# hail-met-v0.net
KiCad netlist of a schematic drawn in EAGLE
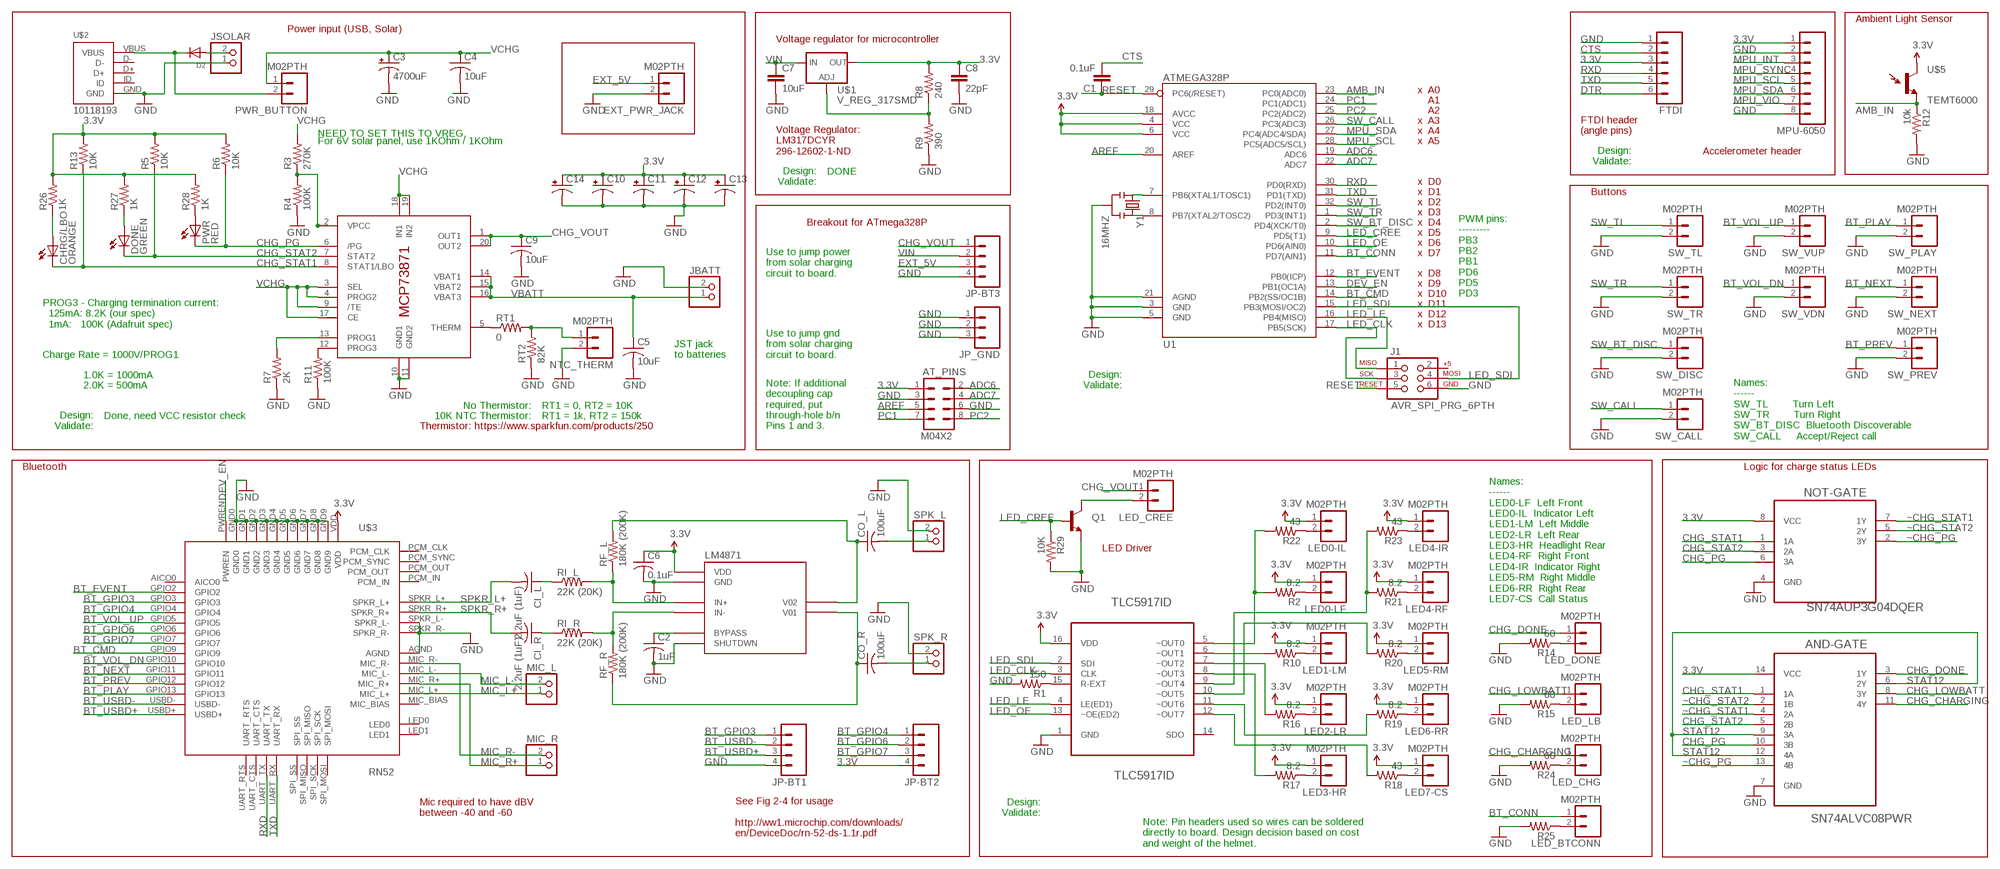
[diagram p0: schematic, sheet 1]

(export (version "E")
  (design (tool "Eeschema 10.0.6"))
  (components
    (comp (ref "AND-GATE")
      (value "SN74ALVC08PWR")
      (footprint "eagle-import:SOP65P640X120-14N")
      (libsource (lib "eagle-import") (part "SN74ALVC08PWR"))
    )
    (comp (ref "AT_PINS")
      (value "M04X2")
      (footprint "eagle-import:2X4")
      (libsource (lib "eagle-import") (part "M04X2"))
    )
    (comp (ref "C1")
      (value "0.1uF")
      (footprint "eagle-import:0805")
      (libsource (lib "eagle-import") (part "CAP0805"))
    )
    (comp (ref "C2")
      (value "1uF")
      (footprint "eagle-import:C0805K")
      (libsource (lib "eagle-import") (part "C-USC0805K"))
    )
    (comp (ref "C3")
      (value "4700uF")
      (footprint "eagle-import:E5-13")
      (libsource (lib "eagle-import") (part "CPOL-USE5-13"))
    )
    (comp (ref "C4")
      (value "10uF")
      (footprint "eagle-import:C0805K")
      (libsource (lib "eagle-import") (part "C-USC0805K"))
    )
    (comp (ref "C5")
      (value "10uF")
      (footprint "eagle-import:C0805K")
      (libsource (lib "eagle-import") (part "rcl_C-USC0805K"))
    )
    (comp (ref "C6")
      (value "0.1uF")
      (footprint "eagle-import:C0805K")
      (libsource (lib "eagle-import") (part "C-USC0805K"))
    )
    (comp (ref "C7")
      (value "10uF")
      (footprint "eagle-import:0805")
      (libsource (lib "eagle-import") (part "CAP0805"))
    )
    (comp (ref "C8")
      (value "22pF")
      (footprint "eagle-import:0805")
      (libsource (lib "eagle-import") (part "CAP0805"))
    )
    (comp (ref "C9")
      (value "10uF")
      (footprint "eagle-import:C0805K")
      (libsource (lib "eagle-import") (part "C-USC0805K"))
    )
    (comp (ref "C10")
      (value "CAP_POLPTH1")
      (footprint "eagle-import:CPOL-RADIAL-100UF-25V")
      (libsource (lib "eagle-import") (part "CAP_POLPTH1"))
    )
    (comp (ref "C11")
      (value "CAP_POLPTH1")
      (footprint "eagle-import:CPOL-RADIAL-100UF-25V")
      (libsource (lib "eagle-import") (part "CAP_POLPTH1"))
    )
    (comp (ref "C12")
      (value "CAP_POLPTH1")
      (footprint "eagle-import:CPOL-RADIAL-100UF-25V")
      (libsource (lib "eagle-import") (part "CAP_POLPTH1"))
    )
    (comp (ref "C13")
      (value "CAP_POLPTH1")
      (footprint "eagle-import:CPOL-RADIAL-100UF-25V")
      (libsource (lib "eagle-import") (part "CAP_POLPTH1"))
    )
    (comp (ref "C14")
      (value "CAP_POLPTH1")
      (footprint "eagle-import:CPOL-RADIAL-100UF-25V")
      (libsource (lib "eagle-import") (part "CAP_POLPTH1"))
    )
    (comp (ref "CHRG/LBO")
      (value "ORANGE")
      (footprint "eagle-import:CHIP-LED0805")
      (libsource (lib "eagle-import") (part "LEDCHIP-LED0805"))
    )
    (comp (ref "CI_L")
      (value "2.2uF (1uF)")
      (footprint "eagle-import:C0805K")
      (libsource (lib "eagle-import") (part "C-USC0805K"))
    )
    (comp (ref "CI_R")
      (value "2.2uF (1uF)")
      (footprint "eagle-import:C0805K")
      (libsource (lib "eagle-import") (part "C-USC0805K"))
    )
    (comp (ref "CO_L")
      (value "100uF")
      (footprint "eagle-import:C0805K")
      (libsource (lib "eagle-import") (part "C-USC0805K"))
    )
    (comp (ref "CO_R")
      (value "100uF")
      (footprint "eagle-import:C0805K")
      (libsource (lib "eagle-import") (part "C-USC0805K"))
    )
    (comp (ref "D2")
      (value "DIODESOD-123")
      (footprint "eagle-import:SOD-123")
      (libsource (lib "eagle-import") (part "DIODESOD-123"))
    )
    (comp (ref "DONE")
      (value "GREEN")
      (footprint "eagle-import:CHIP-LED0805")
      (libsource (lib "eagle-import") (part "LEDCHIP-LED0805"))
    )
    (comp (ref "EXT_PWR_JACK")
      (value "M02PTH")
      (footprint "eagle-import:1X02")
      (libsource (lib "eagle-import") (part "M02PTH"))
    )
    (comp (ref "FTDI")
      (value "M06LOCK")
      (footprint "eagle-import:1X06_LOCK")
      (libsource (lib "eagle-import") (part "M06LOCK"))
    )
    (comp (ref "IC1")
      (value "MCP73871")
      (footprint "eagle-import:QFN20")
      (libsource (lib "eagle-import") (part "MCP73871"))
    )
    (comp (ref "J1")
      (value "AVR_SPI_PRG_6PTH")
      (footprint "eagle-import:2X3")
      (libsource (lib "eagle-import") (part "AVR_SPI_PRG_6PTH"))
    )
    (comp (ref "JBATT")
      (value "JST_2PIN-SMT")
      (footprint "eagle-import:JST-PH-2-SMT")
      (libsource (lib "eagle-import") (part "JST_2PIN-SMT"))
    )
    (comp (ref "JP-BT1")
      (value "M04LOCK")
      (footprint "eagle-import:1X04_LOCK")
      (libsource (lib "eagle-import") (part "M04LOCK"))
    )
    (comp (ref "JP-BT2")
      (value "M04LOCK")
      (footprint "eagle-import:1X04_LOCK")
      (libsource (lib "eagle-import") (part "M04LOCK"))
    )
    (comp (ref "JP-BT3")
      (value "M04LOCK")
      (footprint "eagle-import:1X04_LOCK")
      (libsource (lib "eagle-import") (part "M04LOCK"))
    )
    (comp (ref "JP_GND")
      (value "M03LOCK")
      (footprint "eagle-import:1X03_LOCK")
      (libsource (lib "eagle-import") (part "M03LOCK"))
    )
    (comp (ref "JSOLAR")
      (value "JST_2PIN-SMT")
      (footprint "eagle-import:JST-PH-2-SMT")
      (libsource (lib "eagle-import") (part "JST_2PIN-SMT"))
    )
    (comp (ref "LED0-IL")
      (value "M02PTH")
      (footprint "eagle-import:1X02")
      (libsource (lib "eagle-import") (part "M02PTH"))
    )
    (comp (ref "LED0-LF")
      (value "M02PTH")
      (footprint "eagle-import:1X02")
      (libsource (lib "eagle-import") (part "M02PTH"))
    )
    (comp (ref "LED1-LM")
      (value "M02PTH")
      (footprint "eagle-import:1X02")
      (libsource (lib "eagle-import") (part "M02PTH"))
    )
    (comp (ref "LED2-LR")
      (value "M02PTH")
      (footprint "eagle-import:1X02")
      (libsource (lib "eagle-import") (part "M02PTH"))
    )
    (comp (ref "LED3-HR")
      (value "M02PTH")
      (footprint "eagle-import:1X02")
      (libsource (lib "eagle-import") (part "M02PTH"))
    )
    (comp (ref "LED4-IR")
      (value "M02PTH")
      (footprint "eagle-import:1X02")
      (libsource (lib "eagle-import") (part "M02PTH"))
    )
    (comp (ref "LED4-RF")
      (value "M02PTH")
      (footprint "eagle-import:1X02")
      (libsource (lib "eagle-import") (part "M02PTH"))
    )
    (comp (ref "LED5-RM")
      (value "M02PTH")
      (footprint "eagle-import:1X02")
      (libsource (lib "eagle-import") (part "M02PTH"))
    )
    (comp (ref "LED6-RR")
      (value "M02PTH")
      (footprint "eagle-import:1X02")
      (libsource (lib "eagle-import") (part "M02PTH"))
    )
    (comp (ref "LED7-CS")
      (value "M02PTH")
      (footprint "eagle-import:1X02")
      (libsource (lib "eagle-import") (part "M02PTH"))
    )
    (comp (ref "LED_BTCONN")
      (value "M02PTH")
      (footprint "eagle-import:1X02")
      (libsource (lib "eagle-import") (part "M02PTH"))
    )
    (comp (ref "LED_CHG")
      (value "M02PTH")
      (footprint "eagle-import:1X02")
      (libsource (lib "eagle-import") (part "M02PTH"))
    )
    (comp (ref "LED_CREE")
      (value "M02PTH")
      (footprint "eagle-import:1X02")
      (libsource (lib "eagle-import") (part "M02PTH"))
    )
    (comp (ref "LED_DONE")
      (value "M02PTH")
      (footprint "eagle-import:1X02")
      (libsource (lib "eagle-import") (part "M02PTH"))
    )
    (comp (ref "LED_LB")
      (value "M02PTH")
      (footprint "eagle-import:1X02")
      (libsource (lib "eagle-import") (part "M02PTH"))
    )
    (comp (ref "LM4871")
      (value "LM4871")
      (footprint "eagle-import:SO08")
      (libsource (lib "eagle-import") (part "LM4871"))
    )
    (comp (ref "MIC_L")
      (value "JST_2PIN-SMT")
      (footprint "eagle-import:JST-PH-2-SMT")
      (libsource (lib "eagle-import") (part "JST_2PIN-SMT"))
    )
    (comp (ref "MIC_R")
      (value "JST_2PIN-SMT")
      (footprint "eagle-import:JST-PH-2-SMT")
      (libsource (lib "eagle-import") (part "JST_2PIN-SMT"))
    )
    (comp (ref "MPU-6050")
      (value "M08LOCK")
      (footprint "eagle-import:1X08_LOCK")
      (libsource (lib "eagle-import") (part "M08LOCK"))
    )
    (comp (ref "NOT-GATE")
      (value "SN74AUP3G04DQER")
      (footprint "eagle-import:SON35P100X140X40-8N")
      (libsource (lib "eagle-import") (part "SN74AUP3G04DQER"))
    )
    (comp (ref "NTC_THERM")
      (value "M02PTH")
      (footprint "eagle-import:1X02")
      (libsource (lib "eagle-import") (part "M02PTH"))
    )
    (comp (ref "PWR")
      (value "RED")
      (footprint "eagle-import:CHIP-LED0805")
      (libsource (lib "eagle-import") (part "LEDCHIP-LED0805"))
    )
    (comp (ref "PWR_BUTTON")
      (value "M02PTH")
      (footprint "eagle-import:1X02")
      (libsource (lib "eagle-import") (part "M02PTH"))
    )
    (comp (ref "Q1")
      (value "TRANSISTOR_NPNSOT23-3")
      (footprint "eagle-import:SOT23-3")
      (libsource (lib "eagle-import") (part "TRANSISTOR_NPNSOT23-3"))
    )
    (comp (ref "R1")
      (value "150")
      (footprint "eagle-import:0805")
      (libsource (lib "eagle-import") (part "RESISTOR0805-RES"))
    )
    (comp (ref "R2")
      (value "8.2")
      (footprint "eagle-import:0805")
      (libsource (lib "eagle-import") (part "RESISTOR0805-RES"))
    )
    (comp (ref "R3")
      (value "270K")
      (footprint "eagle-import:0805")
      (libsource (lib "eagle-import") (part "RESISTOR0805-RES"))
    )
    (comp (ref "R4")
      (value "100K")
      (footprint "eagle-import:0805")
      (libsource (lib "eagle-import") (part "RESISTOR0805-RES"))
    )
    (comp (ref "R5")
      (value "10K")
      (footprint "eagle-import:0805")
      (libsource (lib "eagle-import") (part "RESISTOR0805-RES"))
    )
    (comp (ref "R6")
      (value "10K")
      (footprint "eagle-import:0805")
      (libsource (lib "eagle-import") (part "RESISTOR0805-RES"))
    )
    (comp (ref "R7")
      (value "2K")
      (footprint "eagle-import:0805")
      (libsource (lib "eagle-import") (part "RESISTOR0805-RES"))
    )
    (comp (ref "R8")
      (value "240")
      (footprint "eagle-import:0805")
      (libsource (lib "eagle-import") (part "RESISTOR0805-RES"))
    )
    (comp (ref "R9")
      (value "390")
      (footprint "eagle-import:0805")
      (libsource (lib "eagle-import") (part "RESISTOR0805-RES"))
    )
    (comp (ref "R10")
      (value "8.2")
      (footprint "eagle-import:0805")
      (libsource (lib "eagle-import") (part "RESISTOR0805-RES"))
    )
    (comp (ref "R11")
      (value "100K")
      (footprint "eagle-import:0805")
      (libsource (lib "eagle-import") (part "RESISTOR0805-RES"))
    )
    (comp (ref "R12")
      (value "10k")
      (footprint "eagle-import:0805")
      (libsource (lib "eagle-import") (part "RESISTOR0805-RES"))
    )
    (comp (ref "R13")
      (value "10K")
      (footprint "eagle-import:0805")
      (libsource (lib "eagle-import") (part "RESISTOR0805-RES"))
    )
    (comp (ref "R14")
      (value "60")
      (footprint "eagle-import:0805")
      (libsource (lib "eagle-import") (part "RESISTOR0805-RES"))
    )
    (comp (ref "R15")
      (value "60")
      (footprint "eagle-import:0805")
      (libsource (lib "eagle-import") (part "RESISTOR0805-RES"))
    )
    (comp (ref "R16")
      (value "8.2")
      (footprint "eagle-import:0805")
      (libsource (lib "eagle-import") (part "RESISTOR0805-RES"))
    )
    (comp (ref "R17")
      (value "8.2")
      (footprint "eagle-import:0805")
      (libsource (lib "eagle-import") (part "RESISTOR0805-RES"))
    )
    (comp (ref "R18")
      (value "43")
      (footprint "eagle-import:0805")
      (libsource (lib "eagle-import") (part "RESISTOR0805-RES"))
    )
    (comp (ref "R19")
      (value "8.2")
      (footprint "eagle-import:0805")
      (libsource (lib "eagle-import") (part "RESISTOR0805-RES"))
    )
    (comp (ref "R20")
      (value "8.2")
      (footprint "eagle-import:0805")
      (libsource (lib "eagle-import") (part "RESISTOR0805-RES"))
    )
    (comp (ref "R21")
      (value "8.2")
      (footprint "eagle-import:0805")
      (libsource (lib "eagle-import") (part "RESISTOR0805-RES"))
    )
    (comp (ref "R22")
      (value "43")
      (footprint "eagle-import:0805")
      (libsource (lib "eagle-import") (part "RESISTOR0805-RES"))
    )
    (comp (ref "R23")
      (value "43")
      (footprint "eagle-import:0805")
      (libsource (lib "eagle-import") (part "RESISTOR0805-RES"))
    )
    (comp (ref "R24")
      (value "60")
      (footprint "eagle-import:0805")
      (libsource (lib "eagle-import") (part "RESISTOR0805-RES"))
    )
    (comp (ref "R25")
      (value "RESISTOR0805-RES")
      (footprint "eagle-import:0805")
      (libsource (lib "eagle-import") (part "RESISTOR0805-RES"))
    )
    (comp (ref "R26")
      (value "1K")
      (footprint "eagle-import:0805")
      (libsource (lib "eagle-import") (part "RESISTOR0805-RES"))
    )
    (comp (ref "R27")
      (value "1K")
      (footprint "eagle-import:0805")
      (libsource (lib "eagle-import") (part "RESISTOR0805-RES"))
    )
    (comp (ref "R28")
      (value "1K")
      (footprint "eagle-import:0805")
      (libsource (lib "eagle-import") (part "RESISTOR0805-RES"))
    )
    (comp (ref "R29")
      (value "10K")
      (footprint "eagle-import:0805")
      (libsource (lib "eagle-import") (part "RESISTOR0805-RES"))
    )
    (comp (ref "RF_L")
      (value "180K (200K)")
      (footprint "eagle-import:0805")
      (libsource (lib "eagle-import") (part "RESISTOR0805-RES"))
    )
    (comp (ref "RF_R")
      (value "180K (200K)")
      (footprint "eagle-import:0805")
      (libsource (lib "eagle-import") (part "RESISTOR0805-RES"))
    )
    (comp (ref "RI_L")
      (value "22K (20K)")
      (footprint "eagle-import:0805")
      (libsource (lib "eagle-import") (part "RESISTOR0805-RES"))
    )
    (comp (ref "RI_R")
      (value "22K (20K)")
      (footprint "eagle-import:0805")
      (libsource (lib "eagle-import") (part "RESISTOR0805-RES"))
    )
    (comp (ref "RT1")
      (value "0")
      (footprint "eagle-import:0805")
      (libsource (lib "eagle-import") (part "RESISTOR0805-RES"))
    )
    (comp (ref "RT2")
      (value "82K")
      (footprint "eagle-import:0805")
      (libsource (lib "eagle-import") (part "RESISTOR0805-RES"))
    )
    (comp (ref "SPK_L")
      (value "JST_2PIN-SMT")
      (footprint "eagle-import:JST-PH-2-SMT")
      (libsource (lib "eagle-import") (part "JST_2PIN-SMT"))
    )
    (comp (ref "SPK_R")
      (value "JST_2PIN-SMT")
      (footprint "eagle-import:JST-PH-2-SMT")
      (libsource (lib "eagle-import") (part "JST_2PIN-SMT"))
    )
    (comp (ref "SW_CALL")
      (value "M02PTH")
      (footprint "eagle-import:1X02")
      (libsource (lib "eagle-import") (part "M02PTH"))
    )
    (comp (ref "SW_DISC")
      (value "M02PTH")
      (footprint "eagle-import:1X02")
      (libsource (lib "eagle-import") (part "M02PTH"))
    )
    (comp (ref "SW_NEXT")
      (value "M02PTH")
      (footprint "eagle-import:1X02")
      (libsource (lib "eagle-import") (part "M02PTH"))
    )
    (comp (ref "SW_PLAY")
      (value "M02PTH")
      (footprint "eagle-import:1X02")
      (libsource (lib "eagle-import") (part "M02PTH"))
    )
    (comp (ref "SW_PREV")
      (value "M02PTH")
      (footprint "eagle-import:1X02")
      (libsource (lib "eagle-import") (part "M02PTH"))
    )
    (comp (ref "SW_TL")
      (value "M02PTH")
      (footprint "eagle-import:1X02")
      (libsource (lib "eagle-import") (part "M02PTH"))
    )
    (comp (ref "SW_TR")
      (value "M02PTH")
      (footprint "eagle-import:1X02")
      (libsource (lib "eagle-import") (part "M02PTH"))
    )
    (comp (ref "SW_VDN")
      (value "M02PTH")
      (footprint "eagle-import:1X02")
      (libsource (lib "eagle-import") (part "M02PTH"))
    )
    (comp (ref "SW_VUP")
      (value "M02PTH")
      (footprint "eagle-import:1X02")
      (libsource (lib "eagle-import") (part "M02PTH"))
    )
    (comp (ref "TLC5917ID")
      (value "TLC5917ID")
      (footprint "eagle-import:SOIC127P600X175-16N")
      (libsource (lib "eagle-import") (part "TLC5917ID"))
    )
    (comp (ref "U$1")
      (value "V_REG_317SMD")
      (footprint "eagle-import:SOT223")
      (libsource (lib "eagle-import") (part "V_REG_317SMD"))
    )
    (comp (ref "U$2")
      (value "10118193")
      (footprint "eagle-import:10118193")
      (libsource (lib "eagle-import") (part "10118193"))
    )
    (comp (ref "U$3")
      (value "RN52")
      (footprint "eagle-import:RN52")
      (libsource (lib "eagle-import") (part "RN52"))
    )
    (comp (ref "U$5")
      (value "TEMT6000")
      (footprint "eagle-import:TEMT6000-SEN")
      (libsource (lib "eagle-import") (part "TEMT6000"))
    )
    (comp (ref "U1")
      (value "ATMEGA328P")
      (footprint "eagle-import:TQFP32-08")
      (libsource (lib "eagle-import") (part "ATMEGA328_SMT"))
    )
    (comp (ref "Y1")
      (value "16MHZ")
      (footprint "eagle-import:RESONATOR-SMD")
      (libsource (lib "eagle-import") (part "RESONATOR16MHZ"))
    )
  )
  (nets
    (net (code "1") (name "/ADC6") (class "Default")
      (node (ref "AT_PINS") (pin "2") (pinfunction "2_2") (pintype "passive"))
      (node (ref "U1") (pin "19") (pinfunction "ADC6_19") (pintype "bidirectional"))
    )
    (net (code "2") (name "/ADC7") (class "Default")
      (node (ref "AT_PINS") (pin "4") (pinfunction "4_4") (pintype "passive"))
      (node (ref "U1") (pin "22") (pinfunction "ADC7_22") (pintype "bidirectional"))
    )
    (net (code "3") (name "/AMB_IN") (class "Default")
      (node (ref "R12") (pin "1") (pinfunction "1_1") (pintype "passive"))
      (node (ref "U$5") (pin "EMITTER") (pinfunction "E1_EMITTER") (pintype "passive"))
      (node (ref "U1") (pin "23") (pinfunction "PC0(ADC0)_23") (pintype "bidirectional"))
    )
    (net (code "4") (name "/AREF") (class "Default")
      (node (ref "AT_PINS") (pin "5") (pinfunction "5_5") (pintype "passive"))
      (node (ref "U1") (pin "20") (pinfunction "AREF_20") (pintype "bidirectional"))
    )
    (net (code "5") (name "/BT_CMD") (class "Default")
      (node (ref "U$3") (pin "GPIO9") (pinfunction "GPIO9_GPIO9") (pintype "bidirectional"))
      (node (ref "U1") (pin "14") (pinfunction "PB2(SS/OC1B)_14") (pintype "bidirectional"))
    )
    (net (code "6") (name "/BT_CONN") (class "Default")
      (node (ref "LED_BTCONN") (pin "1") (pinfunction "1_1") (pintype "passive"))
      (node (ref "U1") (pin "11") (pinfunction "PD7(AIN1)_11") (pintype "bidirectional"))
    )
    (net (code "7") (name "/BT_EVENT") (class "Default")
      (node (ref "U$3") (pin "GPIO2") (pinfunction "GPIO2_GPIO2") (pintype "bidirectional"))
      (node (ref "U1") (pin "12") (pinfunction "PB0(ICP)_12") (pintype "bidirectional"))
    )
    (net (code "8") (name "/BT_GPIO3") (class "Default")
      (node (ref "JP-BT1") (pin "1") (pinfunction "1_1") (pintype "passive"))
      (node (ref "U$3") (pin "GPIO3") (pinfunction "GPIO3_GPIO3") (pintype "bidirectional"))
    )
    (net (code "9") (name "/BT_GPIO4") (class "Default")
      (node (ref "JP-BT2") (pin "1") (pinfunction "1_1") (pintype "passive"))
      (node (ref "U$3") (pin "GPIO4") (pinfunction "GPIO4_GPIO4") (pintype "bidirectional"))
    )
    (net (code "10") (name "/BT_GPIO6") (class "Default")
      (node (ref "JP-BT2") (pin "2") (pinfunction "2_2") (pintype "passive"))
      (node (ref "U$3") (pin "GPIO6") (pinfunction "GPIO6_GPIO6") (pintype "bidirectional"))
    )
    (net (code "11") (name "/BT_GPIO7") (class "Default")
      (node (ref "JP-BT2") (pin "3") (pinfunction "3_3") (pintype "passive"))
      (node (ref "U$3") (pin "GPIO7") (pinfunction "GPIO7_GPIO7") (pintype "bidirectional"))
    )
    (net (code "12") (name "/BT_NEXT") (class "Default")
      (node (ref "SW_NEXT") (pin "1") (pinfunction "1_1") (pintype "passive"))
      (node (ref "U$3") (pin "GPIO11") (pinfunction "GPIO11_GPIO11") (pintype "bidirectional"))
    )
    (net (code "13") (name "/BT_PLAY") (class "Default")
      (node (ref "SW_PLAY") (pin "1") (pinfunction "1_1") (pintype "passive"))
      (node (ref "U$3") (pin "GPIO13") (pinfunction "GPIO13_GPIO13") (pintype "bidirectional"))
    )
    (net (code "14") (name "/BT_PREV") (class "Default")
      (node (ref "SW_PREV") (pin "1") (pinfunction "1_1") (pintype "passive"))
      (node (ref "U$3") (pin "GPIO12") (pinfunction "GPIO12_GPIO12") (pintype "bidirectional"))
    )
    (net (code "15") (name "/BT_USBD+") (class "Default")
      (node (ref "JP-BT1") (pin "3") (pinfunction "3_3") (pintype "passive"))
      (node (ref "U$3") (pin "USBD+") (pinfunction "USBD+_USBD+") (pintype "bidirectional"))
    )
    (net (code "16") (name "/BT_USBD-") (class "Default")
      (node (ref "JP-BT1") (pin "2") (pinfunction "2_2") (pintype "passive"))
      (node (ref "U$3") (pin "USBD-") (pinfunction "USBD-_USBD-") (pintype "bidirectional"))
    )
    (net (code "17") (name "/BT_VOL_DN") (class "Default")
      (node (ref "SW_VDN") (pin "1") (pinfunction "1_1") (pintype "passive"))
      (node (ref "U$3") (pin "GPIO10") (pinfunction "GPIO10_GPIO10") (pintype "bidirectional"))
    )
    (net (code "18") (name "/BT_VOL_UP") (class "Default")
      (node (ref "SW_VUP") (pin "1") (pinfunction "1_1") (pintype "passive"))
      (node (ref "U$3") (pin "GPIO5") (pinfunction "GPIO5_GPIO5") (pintype "bidirectional"))
    )
    (net (code "19") (name "/CHG_CHARGING") (class "Default")
      (node (ref "AND-GATE") (pin "11") (pinfunction "4Y_11") (pintype "output"))
      (node (ref "LED_CHG") (pin "1") (pinfunction "1_1") (pintype "passive"))
    )
    (net (code "20") (name "/CHG_DONE") (class "Default")
      (node (ref "AND-GATE") (pin "3") (pinfunction "1Y_3") (pintype "output"))
      (node (ref "LED_DONE") (pin "1") (pinfunction "1_1") (pintype "passive"))
    )
    (net (code "21") (name "/CHG_LOWBATT") (class "Default")
      (node (ref "AND-GATE") (pin "8") (pinfunction "3Y_8") (pintype "output"))
      (node (ref "LED_LB") (pin "1") (pinfunction "1_1") (pintype "passive"))
    )
    (net (code "22") (name "/CHG_PG") (class "Default")
      (node (ref "AND-GATE") (pin "10") (pinfunction "3B_10") (pintype "input"))
      (node (ref "IC1") (pin "6") (pinfunction "/PG_6") (pintype "output"))
      (node (ref "NOT-GATE") (pin "6") (pinfunction "3A_6") (pintype "input"))
      (node (ref "PWR") (pin "C") (pinfunction "C_C") (pintype "passive"))
      (node (ref "R6") (pin "1") (pinfunction "1_1") (pintype "passive"))
    )
    (net (code "23") (name "/CHG_STAT1") (class "Default")
      (node (ref "AND-GATE") (pin "1") (pinfunction "1A_1") (pintype "input"))
      (node (ref "CHRG/LBO") (pin "C") (pinfunction "C_C") (pintype "passive"))
      (node (ref "IC1") (pin "8") (pinfunction "STAT1/LBO_8") (pintype "output"))
      (node (ref "NOT-GATE") (pin "1") (pinfunction "1A_1") (pintype "input"))
      (node (ref "R13") (pin "1") (pinfunction "1_1") (pintype "passive"))
    )
    (net (code "24") (name "/CHG_STAT2") (class "Default")
      (node (ref "AND-GATE") (pin "5") (pinfunction "2B_5") (pintype "input"))
      (node (ref "DONE") (pin "C") (pinfunction "C_C") (pintype "passive"))
      (node (ref "IC1") (pin "7") (pinfunction "STAT2_7") (pintype "output"))
      (node (ref "NOT-GATE") (pin "3") (pinfunction "2A_3") (pintype "input"))
      (node (ref "R5") (pin "1") (pinfunction "1_1") (pintype "passive"))
    )
    (net (code "25") (name "/CHG_VOUT") (class "Default")
      (node (ref "C9") (pin "1") (pinfunction "1_1") (pintype "passive"))
      (node (ref "IC1") (pin "1") (pinfunction "OUT1_1") (pintype "output"))
      (node (ref "IC1") (pin "20") (pinfunction "OUT2_20") (pintype "output"))
      (node (ref "JP-BT3") (pin "1") (pinfunction "1_1") (pintype "passive"))
      (node (ref "LED_CREE") (pin "1") (pinfunction "1_1") (pintype "passive"))
    )
    (net (code "26") (name "/CTS") (class "Default")
      (node (ref "C1") (pin "2") (pinfunction "2_2") (pintype "passive"))
      (node (ref "FTDI") (pin "2") (pinfunction "2_2") (pintype "passive"))
    )
    (net (code "27") (name "/DEV_EN") (class "Default")
      (node (ref "U$3") (pin "PWREN") (pinfunction "PWREN_PWREN") (pintype "bidirectional"))
      (node (ref "U1") (pin "13") (pinfunction "PB1(OC1A)_13") (pintype "bidirectional"))
    )
    (net (code "28") (name "/DTR") (class "Default")
      (node (ref "FTDI") (pin "6") (pinfunction "6_6") (pintype "passive"))
    )
    (net (code "29") (name "/EXT_5V") (class "Default")
      (node (ref "EXT_PWR_JACK") (pin "1") (pinfunction "1_1") (pintype "passive"))
      (node (ref "JP-BT3") (pin "3") (pinfunction "3_3") (pintype "passive"))
    )
    (net (code "30") (name "/LED_CLK") (class "Default")
      (node (ref "J1") (pin "3") (pinfunction "3_3") (pintype "passive"))
      (node (ref "TLC5917ID") (pin "3") (pinfunction "CLK_3") (pintype "input"))
      (node (ref "U1") (pin "17") (pinfunction "PB5(SCK)_17") (pintype "bidirectional"))
    )
    (net (code "31") (name "/LED_CREE") (class "Default")
      (node (ref "Q1") (pin "1") (pinfunction "B_1") (pintype "passive"))
      (node (ref "R29") (pin "1") (pinfunction "1_1") (pintype "passive"))
      (node (ref "U1") (pin "9") (pinfunction "PD5(T1)_9") (pintype "bidirectional"))
    )
    (net (code "32") (name "/LED_LE") (class "Default")
      (node (ref "J1") (pin "1") (pinfunction "1_1") (pintype "passive"))
      (node (ref "TLC5917ID") (pin "4") (pinfunction "LE(ED1)_4") (pintype "input"))
      (node (ref "U1") (pin "16") (pinfunction "PB4(MISO)_16") (pintype "bidirectional"))
    )
    (net (code "33") (name "/LED_OE") (class "Default")
      (node (ref "TLC5917ID") (pin "13") (pinfunction "~{OE(ED2})_13") (pintype "input"))
      (node (ref "U1") (pin "10") (pinfunction "PD6(AIN0)_10") (pintype "bidirectional"))
    )
    (net (code "34") (name "/LED_SDI") (class "Default")
      (node (ref "J1") (pin "4") (pinfunction "4_4") (pintype "passive"))
      (node (ref "TLC5917ID") (pin "2") (pinfunction "SDI_2") (pintype "input"))
      (node (ref "U1") (pin "15") (pinfunction "PB3(MOSI/OC2)_15") (pintype "bidirectional"))
    )
    (net (code "35") (name "/MIC_L+") (class "Default")
      (node (ref "MIC_L") (pin "1") (pinfunction "2_1") (pintype "passive"))
      (node (ref "U$3") (pin "MIC_L+") (pinfunction "MIC_L+_MIC_L+") (pintype "bidirectional"))
    )
    (net (code "36") (name "/MIC_L-") (class "Default")
      (node (ref "MIC_L") (pin "2") (pinfunction "1_2") (pintype "passive"))
      (node (ref "U$3") (pin "MIC_L-") (pinfunction "MIC_L-_MIC_L-") (pintype "bidirectional"))
    )
    (net (code "37") (name "/MIC_R+") (class "Default")
      (node (ref "MIC_R") (pin "1") (pinfunction "2_1") (pintype "passive"))
      (node (ref "U$3") (pin "MIC_R+") (pinfunction "MIC_R+_MIC_R+") (pintype "bidirectional"))
    )
    (net (code "38") (name "/MIC_R-") (class "Default")
      (node (ref "MIC_R") (pin "2") (pinfunction "1_2") (pintype "passive"))
      (node (ref "U$3") (pin "MIC_R-") (pinfunction "MIC_R-_MIC_R-") (pintype "bidirectional"))
    )
    (net (code "39") (name "/MPU_INT") (class "Default")
      (node (ref "MPU-6050") (pin "3") (pinfunction "3_3") (pintype "passive"))
    )
    (net (code "40") (name "/MPU_SCL") (class "Default")
      (node (ref "MPU-6050") (pin "5") (pinfunction "5_5") (pintype "passive"))
      (node (ref "U1") (pin "28") (pinfunction "PC5(ADC5/SCL)_28") (pintype "bidirectional"))
    )
    (net (code "41") (name "/MPU_SDA") (class "Default")
      (node (ref "MPU-6050") (pin "6") (pinfunction "6_6") (pintype "passive"))
      (node (ref "U1") (pin "27") (pinfunction "PC4(ADC4/SDA)_27") (pintype "bidirectional"))
    )
    (net (code "42") (name "/MPU_SYNC") (class "Default")
      (node (ref "MPU-6050") (pin "4") (pinfunction "4_4") (pintype "passive"))
    )
    (net (code "43") (name "/MPU_VIO") (class "Default")
      (node (ref "MPU-6050") (pin "7") (pinfunction "7_7") (pintype "passive"))
    )
    (net (code "44") (name "/PC1") (class "Default")
      (node (ref "AT_PINS") (pin "7") (pinfunction "7_7") (pintype "passive"))
      (node (ref "U1") (pin "24") (pinfunction "PC1(ADC1)_24") (pintype "bidirectional"))
    )
    (net (code "45") (name "/PC2") (class "Default")
      (node (ref "AT_PINS") (pin "8") (pinfunction "8_8") (pintype "passive"))
      (node (ref "U1") (pin "25") (pinfunction "PC2(ADC2)_25") (pintype "bidirectional"))
    )
    (net (code "46") (name "/RESET") (class "Default")
      (node (ref "C1") (pin "1") (pinfunction "1_1") (pintype "passive"))
      (node (ref "J1") (pin "5") (pinfunction "5_5") (pintype "passive"))
      (node (ref "U1") (pin "29") (pinfunction "PC6(/RESET)_29") (pintype "bidirectional"))
    )
    (net (code "47") (name "/RXD") (class "Default")
      (node (ref "FTDI") (pin "4") (pinfunction "4_4") (pintype "passive"))
      (node (ref "U$3") (pin "UART_TX") (pinfunction "UART_TX_UART_TX") (pintype "bidirectional"))
      (node (ref "U1") (pin "30") (pinfunction "PD0(RXD)_30") (pintype "bidirectional"))
    )
    (net (code "48") (name "/SPKR_L+") (class "Default")
      (node (ref "CI_L") (pin "2") (pinfunction "2_2") (pintype "passive"))
      (node (ref "U$3") (pin "SPKR_L+") (pinfunction "SPKR_L+_SPKR_L+") (pintype "bidirectional"))
    )
    (net (code "49") (name "/SPKR_R+") (class "Default")
      (node (ref "CI_R") (pin "2") (pinfunction "2_2") (pintype "passive"))
      (node (ref "U$3") (pin "SPKR_R+") (pinfunction "SPKR_R+_SPKR_R+") (pintype "bidirectional"))
    )
    (net (code "50") (name "/STAT12") (class "Default")
      (node (ref "AND-GATE") (pin "12") (pinfunction "4A_12") (pintype "input"))
      (node (ref "AND-GATE") (pin "6") (pinfunction "2Y_6") (pintype "output"))
      (node (ref "AND-GATE") (pin "9") (pinfunction "3A_9") (pintype "input"))
    )
    (net (code "51") (name "/SW_BT_DISC") (class "Default")
      (node (ref "SW_DISC") (pin "1") (pinfunction "1_1") (pintype "passive"))
      (node (ref "U1") (pin "2") (pinfunction "PD4(XCK/T0)_2") (pintype "bidirectional"))
    )
    (net (code "52") (name "/SW_CALL") (class "Default")
      (node (ref "SW_CALL") (pin "1") (pinfunction "1_1") (pintype "passive"))
      (node (ref "U1") (pin "26") (pinfunction "PC3(ADC3)_26") (pintype "bidirectional"))
    )
    (net (code "53") (name "/SW_TL") (class "Default")
      (node (ref "SW_TL") (pin "1") (pinfunction "1_1") (pintype "passive"))
      (node (ref "U1") (pin "32") (pinfunction "PD2(INT0)_32") (pintype "bidirectional"))
    )
    (net (code "54") (name "/SW_TR") (class "Default")
      (node (ref "SW_TR") (pin "1") (pinfunction "1_1") (pintype "passive"))
      (node (ref "U1") (pin "1") (pinfunction "PD3(INT1)_1") (pintype "bidirectional"))
    )
    (net (code "55") (name "/TXD") (class "Default")
      (node (ref "FTDI") (pin "5") (pinfunction "5_5") (pintype "passive"))
      (node (ref "U$3") (pin "UART_RX") (pinfunction "UART_RX_UART_RX") (pintype "bidirectional"))
      (node (ref "U1") (pin "31") (pinfunction "PD1(TXD)_31") (pintype "bidirectional"))
    )
    (net (code "56") (name "/VBATT") (class "Default")
      (node (ref "C5") (pin "1") (pinfunction "1_1") (pintype "passive"))
      (node (ref "IC1") (pin "14") (pinfunction "VBAT1_14") (pintype "output"))
      (node (ref "IC1") (pin "15") (pinfunction "VBAT2_15") (pintype "output"))
      (node (ref "IC1") (pin "16") (pinfunction "VBAT3_16") (pintype "output"))
      (node (ref "JBATT") (pin "1") (pinfunction "2_1") (pintype "passive"))
    )
    (net (code "57") (name "/VCHG") (class "Default")
      (node (ref "C3") (pin "+") (pinfunction "+_+") (pintype "passive"))
      (node (ref "C4") (pin "1") (pinfunction "1_1") (pintype "passive"))
      (node (ref "IC1") (pin "17") (pinfunction "CE_17") (pintype "input"))
      (node (ref "IC1") (pin "18") (pinfunction "IN1_18") (pintype "input"))
      (node (ref "IC1") (pin "19") (pinfunction "IN2_19") (pintype "input"))
      (node (ref "IC1") (pin "3") (pinfunction "SEL_3") (pintype "input"))
      (node (ref "IC1") (pin "4") (pinfunction "PROG2_4") (pintype "input"))
      (node (ref "IC1") (pin "9") (pinfunction "/TE_9") (pintype "input"))
      (node (ref "PWR_BUTTON") (pin "1") (pinfunction "1_1") (pintype "passive"))
      (node (ref "R3") (pin "2") (pinfunction "2_2") (pintype "passive"))
    )
    (net (code "58") (name "/VIN") (class "Default")
      (node (ref "C7") (pin "1") (pinfunction "1_1") (pintype "passive"))
      (node (ref "JP-BT3") (pin "2") (pinfunction "2_2") (pintype "passive"))
      (node (ref "U$1") (pin "3") (pinfunction "IN_3") (pintype "input"))
    )
    (net (code "59") (name "/~{CHG_PG}") (class "Default")
      (node (ref "AND-GATE") (pin "13") (pinfunction "4B_13") (pintype "input"))
      (node (ref "NOT-GATE") (pin "2") (pinfunction "3Y_2") (pintype "output"))
    )
    (net (code "60") (name "/~{CHG_STAT1}") (class "Default")
      (node (ref "AND-GATE") (pin "4") (pinfunction "2A_4") (pintype "input"))
      (node (ref "NOT-GATE") (pin "7") (pinfunction "1Y_7") (pintype "output"))
    )
    (net (code "61") (name "/~{CHG_STAT2}") (class "Default")
      (node (ref "AND-GATE") (pin "2") (pinfunction "1B_2") (pintype "input"))
      (node (ref "NOT-GATE") (pin "5") (pinfunction "2Y_5") (pintype "output"))
    )
    (net (code "62") (name "3.3V") (class "Default")
      (node (ref "AND-GATE") (pin "14") (pinfunction "VCC_14") (pintype "power_in"))
      (node (ref "AT_PINS") (pin "1") (pinfunction "1_1") (pintype "passive"))
      (node (ref "C10") (pin "1") (pinfunction "+_1") (pintype "passive"))
      (node (ref "C11") (pin "1") (pinfunction "+_1") (pintype "passive"))
      (node (ref "C12") (pin "1") (pinfunction "+_1") (pintype "passive"))
      (node (ref "C13") (pin "1") (pinfunction "+_1") (pintype "passive"))
      (node (ref "C14") (pin "1") (pinfunction "+_1") (pintype "passive"))
      (node (ref "C6") (pin "1") (pinfunction "1_1") (pintype "passive"))
      (node (ref "C8") (pin "1") (pinfunction "1_1") (pintype "passive"))
      (node (ref "FTDI") (pin "3") (pinfunction "3_3") (pintype "passive"))
      (node (ref "JP-BT2") (pin "4") (pinfunction "4_4") (pintype "passive"))
      (node (ref "LED0-IL") (pin "1") (pinfunction "1_1") (pintype "passive"))
      (node (ref "LED0-LF") (pin "1") (pinfunction "1_1") (pintype "passive"))
      (node (ref "LED1-LM") (pin "1") (pinfunction "1_1") (pintype "passive"))
      (node (ref "LED2-LR") (pin "1") (pinfunction "1_1") (pintype "passive"))
      (node (ref "LED3-HR") (pin "1") (pinfunction "1_1") (pintype "passive"))
      (node (ref "LED4-IR") (pin "1") (pinfunction "1_1") (pintype "passive"))
      (node (ref "LED4-RF") (pin "1") (pinfunction "1_1") (pintype "passive"))
      (node (ref "LED5-RM") (pin "1") (pinfunction "1_1") (pintype "passive"))
      (node (ref "LED6-RR") (pin "1") (pinfunction "1_1") (pintype "passive"))
      (node (ref "LED7-CS") (pin "1") (pinfunction "1_1") (pintype "passive"))
      (node (ref "LM4871") (pin "6") (pinfunction "VDD_6") (pintype "bidirectional"))
      (node (ref "MPU-6050") (pin "1") (pinfunction "1_1") (pintype "passive"))
      (node (ref "NOT-GATE") (pin "8") (pinfunction "VCC_8") (pintype "power_in"))
      (node (ref "R13") (pin "2") (pinfunction "2_2") (pintype "passive"))
      (node (ref "R26") (pin "2") (pinfunction "2_2") (pintype "passive"))
      (node (ref "R27") (pin "2") (pinfunction "2_2") (pintype "passive"))
      (node (ref "R28") (pin "2") (pinfunction "2_2") (pintype "passive"))
      (node (ref "R5") (pin "2") (pinfunction "2_2") (pintype "passive"))
      (node (ref "R6") (pin "2") (pinfunction "2_2") (pintype "passive"))
      (node (ref "R8") (pin "2") (pinfunction "2_2") (pintype "passive"))
      (node (ref "TLC5917ID") (pin "16") (pinfunction "VDD_16") (pintype "power_in"))
      (node (ref "U$1") (pin "2") (pinfunction "OUT_2") (pintype "output"))
      (node (ref "U$3") (pin "VDD") (pinfunction "VDD_VDD") (pintype "bidirectional"))
      (node (ref "U$5") (pin "COLLECTOR") (pinfunction "C1_COLLECTOR") (pintype "passive"))
      (node (ref "U1") (pin "18") (pinfunction "AVCC_18") (pintype "bidirectional"))
      (node (ref "U1") (pin "4") (pinfunction "VCC_4") (pintype "bidirectional"))
      (node (ref "U1") (pin "6") (pinfunction "VCC_6") (pintype "bidirectional"))
    )
    (net (code "63") (name "GND") (class "Default")
      (node (ref "AND-GATE") (pin "7") (pinfunction "GND_7") (pintype "passive"))
      (node (ref "AT_PINS") (pin "3") (pinfunction "3_3") (pintype "passive"))
      (node (ref "AT_PINS") (pin "6") (pinfunction "6_6") (pintype "passive"))
      (node (ref "C10") (pin "2") (pinfunction "-_2") (pintype "passive"))
      (node (ref "C11") (pin "2") (pinfunction "-_2") (pintype "passive"))
      (node (ref "C12") (pin "2") (pinfunction "-_2") (pintype "passive"))
      (node (ref "C13") (pin "2") (pinfunction "-_2") (pintype "passive"))
      (node (ref "C14") (pin "2") (pinfunction "-_2") (pintype "passive"))
      (node (ref "C2") (pin "2") (pinfunction "2_2") (pintype "passive"))
      (node (ref "C3") (pin "-") (pinfunction "-_-") (pintype "passive"))
      (node (ref "C4") (pin "2") (pinfunction "2_2") (pintype "passive"))
      (node (ref "C5") (pin "2") (pinfunction "2_2") (pintype "passive"))
      (node (ref "C6") (pin "2") (pinfunction "2_2") (pintype "passive"))
      (node (ref "C7") (pin "2") (pinfunction "2_2") (pintype "passive"))
      (node (ref "C8") (pin "2") (pinfunction "2_2") (pintype "passive"))
      (node (ref "C9") (pin "2") (pinfunction "2_2") (pintype "passive"))
      (node (ref "EXT_PWR_JACK") (pin "2") (pinfunction "2_2") (pintype "passive"))
      (node (ref "FTDI") (pin "1") (pinfunction "1_1") (pintype "passive"))
      (node (ref "IC1") (pin "10") (pinfunction "GND1_10") (pintype "power_in"))
      (node (ref "IC1") (pin "11") (pinfunction "GND2_11") (pintype "power_in"))
      (node (ref "J1") (pin "6") (pinfunction "6_6") (pintype "passive"))
      (node (ref "JBATT") (pin "2") (pinfunction "1_2") (pintype "passive"))
      (node (ref "JP-BT1") (pin "4") (pinfunction "4_4") (pintype "passive"))
      (node (ref "JP-BT3") (pin "4") (pinfunction "4_4") (pintype "passive"))
      (node (ref "JP_GND") (pin "1") (pinfunction "1_1") (pintype "passive"))
      (node (ref "JP_GND") (pin "2") (pinfunction "2_2") (pintype "passive"))
      (node (ref "JP_GND") (pin "3") (pinfunction "3_3") (pintype "passive"))
      (node (ref "JSOLAR") (pin "1") (pinfunction "2_1") (pintype "passive"))
      (node (ref "LM4871") (pin "1") (pinfunction "SHUTDWN_1") (pintype "bidirectional"))
      (node (ref "LM4871") (pin "7") (pinfunction "GND_7") (pintype "bidirectional"))
      (node (ref "MPU-6050") (pin "2") (pinfunction "2_2") (pintype "passive"))
      (node (ref "MPU-6050") (pin "8") (pinfunction "8_8") (pintype "passive"))
      (node (ref "NOT-GATE") (pin "4") (pinfunction "GND_4") (pintype "passive"))
      (node (ref "NTC_THERM") (pin "2") (pinfunction "2_2") (pintype "passive"))
      (node (ref "Q1") (pin "2") (pinfunction "E_2") (pintype "passive"))
      (node (ref "R1") (pin "2") (pinfunction "2_2") (pintype "passive"))
      (node (ref "R11") (pin "1") (pinfunction "1_1") (pintype "passive"))
      (node (ref "R12") (pin "2") (pinfunction "2_2") (pintype "passive"))
      (node (ref "R14") (pin "2") (pinfunction "2_2") (pintype "passive"))
      (node (ref "R15") (pin "2") (pinfunction "2_2") (pintype "passive"))
      (node (ref "R24") (pin "2") (pinfunction "2_2") (pintype "passive"))
      (node (ref "R25") (pin "2") (pinfunction "2_2") (pintype "passive"))
      (node (ref "R29") (pin "2") (pinfunction "2_2") (pintype "passive"))
      (node (ref "R4") (pin "1") (pinfunction "1_1") (pintype "passive"))
      (node (ref "R7") (pin "1") (pinfunction "1_1") (pintype "passive"))
      (node (ref "R9") (pin "1") (pinfunction "1_1") (pintype "passive"))
      (node (ref "RT2") (pin "1") (pinfunction "1_1") (pintype "passive"))
      (node (ref "SPK_L") (pin "2") (pinfunction "1_2") (pintype "passive"))
      (node (ref "SPK_R") (pin "2") (pinfunction "1_2") (pintype "passive"))
      (node (ref "SW_CALL") (pin "2") (pinfunction "2_2") (pintype "passive"))
      (node (ref "SW_DISC") (pin "2") (pinfunction "2_2") (pintype "passive"))
      (node (ref "SW_NEXT") (pin "2") (pinfunction "2_2") (pintype "passive"))
      (node (ref "SW_PLAY") (pin "2") (pinfunction "2_2") (pintype "passive"))
      (node (ref "SW_PREV") (pin "2") (pinfunction "2_2") (pintype "passive"))
      (node (ref "SW_TL") (pin "2") (pinfunction "2_2") (pintype "passive"))
      (node (ref "SW_TR") (pin "2") (pinfunction "2_2") (pintype "passive"))
      (node (ref "SW_VDN") (pin "2") (pinfunction "2_2") (pintype "passive"))
      (node (ref "SW_VUP") (pin "2") (pinfunction "2_2") (pintype "passive"))
      (node (ref "TLC5917ID") (pin "1") (pinfunction "GND_1") (pintype "passive"))
      (node (ref "U$2") (pin "GND") (pinfunction "GND_GND") (pintype "bidirectional"))
      (node (ref "U$3") (pin "AGND") (pinfunction "AGND_AGND") (pintype "bidirectional"))
      (node (ref "U$3") (pin "GND0") (pinfunction "GND0_GND0") (pintype "bidirectional"))
      (node (ref "U$3") (pin "GND1") (pinfunction "GND1_GND1") (pintype "bidirectional"))
      (node (ref "U$3") (pin "GND2") (pinfunction "GND2_GND2") (pintype "bidirectional"))
      (node (ref "U$3") (pin "GND3") (pinfunction "GND3_GND3") (pintype "bidirectional"))
      (node (ref "U$3") (pin "GND4") (pinfunction "GND4_GND4") (pintype "bidirectional"))
      (node (ref "U$3") (pin "GND5") (pinfunction "GND5_GND5") (pintype "bidirectional"))
      (node (ref "U$3") (pin "GND6") (pinfunction "GND6_GND6") (pintype "bidirectional"))
      (node (ref "U$3") (pin "GND7") (pinfunction "GND7_GND7") (pintype "bidirectional"))
      (node (ref "U$3") (pin "GND8") (pinfunction "GND8_GND8") (pintype "bidirectional"))
      (node (ref "U$3") (pin "GND9") (pinfunction "GND9_GND9") (pintype "bidirectional"))
      (node (ref "U$3") (pin "SPKR_L-") (pinfunction "SPKR_L-_SPKR_L-") (pintype "bidirectional"))
      (node (ref "U$3") (pin "SPKR_R-") (pinfunction "SPKR_R-_SPKR_R-") (pintype "bidirectional"))
      (node (ref "U1") (pin "21") (pinfunction "AGND_21") (pintype "bidirectional"))
      (node (ref "U1") (pin "3") (pinfunction "GND_3") (pintype "bidirectional"))
      (node (ref "U1") (pin "5") (pinfunction "GND_5") (pintype "bidirectional"))
      (node (ref "Y1") (pin "2") (pinfunction "2_2") (pintype "passive"))
    )
    (net (code "64") (name "Net-(CHRG/LBO-PadA)") (class "Default")
      (node (ref "CHRG/LBO") (pin "A") (pinfunction "A_A") (pintype "passive"))
      (node (ref "R26") (pin "1") (pinfunction "1_1") (pintype "passive"))
    )
    (net (code "65") (name "Net-(CI_L-Pad1)") (class "Default")
      (node (ref "CI_L") (pin "1") (pinfunction "1_1") (pintype "passive"))
      (node (ref "RI_L") (pin "1") (pinfunction "1_1") (pintype "passive"))
    )
    (net (code "66") (name "Net-(CI_R-Pad1)") (class "Default")
      (node (ref "CI_R") (pin "1") (pinfunction "1_1") (pintype "passive"))
      (node (ref "RI_R") (pin "1") (pinfunction "1_1") (pintype "passive"))
    )
    (net (code "67") (name "Net-(D2-PadC)") (class "Default")
      (node (ref "D2") (pin "C") (pinfunction "C_C") (pintype "passive"))
      (node (ref "PWR_BUTTON") (pin "2") (pinfunction "2_2") (pintype "passive"))
      (node (ref "U$2") (pin "VBUS") (pinfunction "VBUS_VBUS") (pintype "bidirectional"))
    )
    (net (code "68") (name "Net-(DONE-PadA)") (class "Default")
      (node (ref "DONE") (pin "A") (pinfunction "A_A") (pintype "passive"))
      (node (ref "R27") (pin "1") (pinfunction "1_1") (pintype "passive"))
    )
    (net (code "69") (name "Net-(IC1-PROG1)") (class "Default")
      (node (ref "IC1") (pin "13") (pinfunction "PROG1_13") (pintype "input"))
      (node (ref "R7") (pin "2") (pinfunction "2_2") (pintype "passive"))
    )
    (net (code "70") (name "Net-(IC1-PROG3)") (class "Default")
      (node (ref "IC1") (pin "12") (pinfunction "PROG3_12") (pintype "input"))
      (node (ref "R11") (pin "2") (pinfunction "2_2") (pintype "passive"))
    )
    (net (code "71") (name "Net-(IC1-THERM)") (class "Default")
      (node (ref "IC1") (pin "5") (pinfunction "THERM_5") (pintype "input"))
      (node (ref "RT1") (pin "1") (pinfunction "1_1") (pintype "passive"))
    )
    (net (code "72") (name "Net-(IC1-VPCC)") (class "Default")
      (node (ref "IC1") (pin "2") (pinfunction "VPCC_2") (pintype "input"))
      (node (ref "R3") (pin "1") (pinfunction "1_1") (pintype "passive"))
      (node (ref "R4") (pin "2") (pinfunction "2_2") (pintype "passive"))
    )
    (net (code "73") (name "Net-(JSOLAR-1)") (class "Default")
      (node (ref "D2") (pin "A") (pinfunction "A_A") (pintype "passive"))
      (node (ref "JSOLAR") (pin "2") (pinfunction "1_2") (pintype "passive"))
    )
    (net (code "74") (name "Net-(LED0-IL-Pad2)") (class "Default")
      (node (ref "LED0-IL") (pin "2") (pinfunction "2_2") (pintype "passive"))
      (node (ref "R22") (pin "1") (pinfunction "1_1") (pintype "passive"))
    )
    (net (code "75") (name "Net-(LED0-LF-Pad2)") (class "Default")
      (node (ref "LED0-LF") (pin "2") (pinfunction "2_2") (pintype "passive"))
      (node (ref "R2") (pin "1") (pinfunction "1_1") (pintype "passive"))
    )
    (net (code "76") (name "Net-(LED1-LM-Pad2)") (class "Default")
      (node (ref "LED1-LM") (pin "2") (pinfunction "2_2") (pintype "passive"))
      (node (ref "R10") (pin "1") (pinfunction "1_1") (pintype "passive"))
    )
    (net (code "77") (name "Net-(LED2-LR-Pad2)") (class "Default")
      (node (ref "LED2-LR") (pin "2") (pinfunction "2_2") (pintype "passive"))
      (node (ref "R16") (pin "1") (pinfunction "1_1") (pintype "passive"))
    )
    (net (code "78") (name "Net-(LED3-HR-Pad2)") (class "Default")
      (node (ref "LED3-HR") (pin "2") (pinfunction "2_2") (pintype "passive"))
      (node (ref "R17") (pin "1") (pinfunction "1_1") (pintype "passive"))
    )
    (net (code "79") (name "Net-(LED4-IR-Pad2)") (class "Default")
      (node (ref "LED4-IR") (pin "2") (pinfunction "2_2") (pintype "passive"))
      (node (ref "R23") (pin "1") (pinfunction "1_1") (pintype "passive"))
    )
    (net (code "80") (name "Net-(LED4-RF-Pad2)") (class "Default")
      (node (ref "LED4-RF") (pin "2") (pinfunction "2_2") (pintype "passive"))
      (node (ref "R21") (pin "1") (pinfunction "1_1") (pintype "passive"))
    )
    (net (code "81") (name "Net-(LED5-RM-Pad2)") (class "Default")
      (node (ref "LED5-RM") (pin "2") (pinfunction "2_2") (pintype "passive"))
      (node (ref "R20") (pin "1") (pinfunction "1_1") (pintype "passive"))
    )
    (net (code "82") (name "Net-(LED6-RR-Pad2)") (class "Default")
      (node (ref "LED6-RR") (pin "2") (pinfunction "2_2") (pintype "passive"))
      (node (ref "R19") (pin "1") (pinfunction "1_1") (pintype "passive"))
    )
    (net (code "83") (name "Net-(LED7-CS-Pad2)") (class "Default")
      (node (ref "LED7-CS") (pin "2") (pinfunction "2_2") (pintype "passive"))
      (node (ref "R18") (pin "1") (pinfunction "1_1") (pintype "passive"))
    )
    (net (code "84") (name "Net-(LED_BTCONN-Pad2)") (class "Default")
      (node (ref "LED_BTCONN") (pin "2") (pinfunction "2_2") (pintype "passive"))
      (node (ref "R25") (pin "1") (pinfunction "1_1") (pintype "passive"))
    )
    (net (code "85") (name "Net-(LED_CHG-Pad2)") (class "Default")
      (node (ref "LED_CHG") (pin "2") (pinfunction "2_2") (pintype "passive"))
      (node (ref "R24") (pin "1") (pinfunction "1_1") (pintype "passive"))
    )
    (net (code "86") (name "Net-(LED_DONE-Pad2)") (class "Default")
      (node (ref "LED_DONE") (pin "2") (pinfunction "2_2") (pintype "passive"))
      (node (ref "R14") (pin "1") (pinfunction "1_1") (pintype "passive"))
    )
    (net (code "87") (name "Net-(LED_LB-Pad2)") (class "Default")
      (node (ref "LED_LB") (pin "2") (pinfunction "2_2") (pintype "passive"))
      (node (ref "R15") (pin "1") (pinfunction "1_1") (pintype "passive"))
    )
    (net (code "88") (name "Net-(LM4871-BYPASS)") (class "Default")
      (node (ref "C2") (pin "1") (pinfunction "1_1") (pintype "passive"))
      (node (ref "LM4871") (pin "2") (pinfunction "BYPASS_2") (pintype "bidirectional"))
    )
    (net (code "89") (name "Net-(LM4871-IN+)") (class "Default")
      (node (ref "LM4871") (pin "3") (pinfunction "IN+_3") (pintype "bidirectional"))
      (node (ref "RF_L") (pin "1") (pinfunction "1_1") (pintype "passive"))
      (node (ref "RI_L") (pin "2") (pinfunction "2_2") (pintype "passive"))
    )
    (net (code "90") (name "Net-(LM4871-IN-)") (class "Default")
      (node (ref "LM4871") (pin "4") (pinfunction "IN-_4") (pintype "bidirectional"))
      (node (ref "RF_R") (pin "2") (pinfunction "2_2") (pintype "passive"))
      (node (ref "RI_R") (pin "2") (pinfunction "2_2") (pintype "passive"))
    )
    (net (code "91") (name "Net-(LM4871-V01)") (class "Default")
      (node (ref "CO_R") (pin "1") (pinfunction "1_1") (pintype "passive"))
      (node (ref "LM4871") (pin "5") (pinfunction "V01_5") (pintype "bidirectional"))
      (node (ref "RF_R") (pin "1") (pinfunction "1_1") (pintype "passive"))
    )
    (net (code "92") (name "Net-(LM4871-V02)") (class "Default")
      (node (ref "CO_L") (pin "1") (pinfunction "1_1") (pintype "passive"))
      (node (ref "LM4871") (pin "8") (pinfunction "V02_8") (pintype "bidirectional"))
      (node (ref "RF_L") (pin "2") (pinfunction "2_2") (pintype "passive"))
    )
    (net (code "93") (name "Net-(NTC_THERM-Pad1)") (class "Default")
      (node (ref "NTC_THERM") (pin "1") (pinfunction "1_1") (pintype "passive"))
      (node (ref "RT1") (pin "2") (pinfunction "2_2") (pintype "passive"))
      (node (ref "RT2") (pin "2") (pinfunction "2_2") (pintype "passive"))
    )
    (net (code "94") (name "Net-(PWR-PadA)") (class "Default")
      (node (ref "PWR") (pin "A") (pinfunction "A_A") (pintype "passive"))
      (node (ref "R28") (pin "1") (pinfunction "1_1") (pintype "passive"))
    )
    (net (code "95") (name "Net-(Q1-C)") (class "Default")
      (node (ref "LED_CREE") (pin "2") (pinfunction "2_2") (pintype "passive"))
      (node (ref "Q1") (pin "3") (pinfunction "C_3") (pintype "passive"))
    )
    (net (code "96") (name "Net-(SPK_L-2)") (class "Default")
      (node (ref "CO_L") (pin "2") (pinfunction "2_2") (pintype "passive"))
      (node (ref "SPK_L") (pin "1") (pinfunction "2_1") (pintype "passive"))
    )
    (net (code "97") (name "Net-(SPK_R-2)") (class "Default")
      (node (ref "CO_R") (pin "2") (pinfunction "2_2") (pintype "passive"))
      (node (ref "SPK_R") (pin "1") (pinfunction "2_1") (pintype "passive"))
    )
    (net (code "98") (name "Net-(TLC5917ID-R-EXT)") (class "Default")
      (node (ref "R1") (pin "1") (pinfunction "1_1") (pintype "passive"))
      (node (ref "TLC5917ID") (pin "15") (pinfunction "R-EXT_15") (pintype "passive"))
    )
    (net (code "99") (name "Net-(TLC5917ID-~{OUT0})") (class "Default")
      (node (ref "R2") (pin "2") (pinfunction "2_2") (pintype "passive"))
      (node (ref "R22") (pin "2") (pinfunction "2_2") (pintype "passive"))
      (node (ref "TLC5917ID") (pin "5") (pinfunction "~{OUT0}_5") (pintype "output"))
    )
    (net (code "100") (name "Net-(TLC5917ID-~{OUT1})") (class "Default")
      (node (ref "R10") (pin "2") (pinfunction "2_2") (pintype "passive"))
      (node (ref "TLC5917ID") (pin "6") (pinfunction "~{OUT1}_6") (pintype "output"))
    )
    (net (code "101") (name "Net-(TLC5917ID-~{OUT2})") (class "Default")
      (node (ref "R16") (pin "2") (pinfunction "2_2") (pintype "passive"))
      (node (ref "TLC5917ID") (pin "7") (pinfunction "~{OUT2}_7") (pintype "output"))
    )
    (net (code "102") (name "Net-(TLC5917ID-~{OUT3})") (class "Default")
      (node (ref "R17") (pin "2") (pinfunction "2_2") (pintype "passive"))
      (node (ref "TLC5917ID") (pin "8") (pinfunction "~{OUT3}_8") (pintype "output"))
    )
    (net (code "103") (name "Net-(TLC5917ID-~{OUT4})") (class "Default")
      (node (ref "R21") (pin "2") (pinfunction "2_2") (pintype "passive"))
      (node (ref "R23") (pin "2") (pinfunction "2_2") (pintype "passive"))
      (node (ref "TLC5917ID") (pin "9") (pinfunction "~{OUT4}_9") (pintype "output"))
    )
    (net (code "104") (name "Net-(TLC5917ID-~{OUT5})") (class "Default")
      (node (ref "R20") (pin "2") (pinfunction "2_2") (pintype "passive"))
      (node (ref "TLC5917ID") (pin "10") (pinfunction "~{OUT5}_10") (pintype "output"))
    )
    (net (code "105") (name "Net-(TLC5917ID-~{OUT6})") (class "Default")
      (node (ref "R19") (pin "2") (pinfunction "2_2") (pintype "passive"))
      (node (ref "TLC5917ID") (pin "11") (pinfunction "~{OUT6}_11") (pintype "output"))
    )
    (net (code "106") (name "Net-(TLC5917ID-~{OUT7})") (class "Default")
      (node (ref "R18") (pin "2") (pinfunction "2_2") (pintype "passive"))
      (node (ref "TLC5917ID") (pin "12") (pinfunction "~{OUT7}_12") (pintype "output"))
    )
    (net (code "107") (name "Net-(U$1-ADJ)") (class "Default")
      (node (ref "R8") (pin "1") (pinfunction "1_1") (pintype "passive"))
      (node (ref "R9") (pin "2") (pinfunction "2_2") (pintype "passive"))
      (node (ref "U$1") (pin "1") (pinfunction "ADJ_1") (pintype "input"))
    )
    (net (code "108") (name "Net-(U1-PB6(XTAL1{slash}TOSC1))") (class "Default")
      (node (ref "U1") (pin "7") (pinfunction "PB6(XTAL1/TOSC1)_7") (pintype "bidirectional"))
      (node (ref "Y1") (pin "1") (pinfunction "1_1") (pintype "passive"))
    )
    (net (code "109") (name "Net-(U1-PB7(XTAL2{slash}TOSC2))") (class "Default")
      (node (ref "U1") (pin "8") (pinfunction "PB7(XTAL2/TOSC2)_8") (pintype "bidirectional"))
      (node (ref "Y1") (pin "3") (pinfunction "3_3") (pintype "passive"))
    )
    (net (code "110") (name "unconnected-(J1-Pad2)") (class "Default")
      (node (ref "J1") (pin "2") (pinfunction "2_2") (pintype "passive"))
    )
    (net (code "111") (name "unconnected-(TLC5917ID-SDO-Pad14)") (class "Default")
      (node (ref "TLC5917ID") (pin "14") (pinfunction "SDO_14") (pintype "output"))
    )
    (net (code "112") (name "unconnected-(U$2-PadD+)") (class "Default")
      (node (ref "U$2") (pin "D+") (pinfunction "D+_D+") (pintype "bidirectional"))
    )
    (net (code "113") (name "unconnected-(U$2-PadD-)") (class "Default")
      (node (ref "U$2") (pin "D-") (pinfunction "D-_D-") (pintype "bidirectional"))
    )
    (net (code "114") (name "unconnected-(U$2-PadID)") (class "Default")
      (node (ref "U$2") (pin "ID") (pinfunction "ID_ID") (pintype "bidirectional"))
    )
    (net (code "115") (name "unconnected-(U$3-PadAICO0)") (class "Default")
      (node (ref "U$3") (pin "AICO0") (pinfunction "AICO0_AICO0") (pintype "bidirectional"))
    )
    (net (code "116") (name "unconnected-(U$3-PadLED0)") (class "Default")
      (node (ref "U$3") (pin "LED0") (pinfunction "LED0_LED0") (pintype "bidirectional"))
    )
    (net (code "117") (name "unconnected-(U$3-PadLED1)") (class "Default")
      (node (ref "U$3") (pin "LED1") (pinfunction "LED1_LED1") (pintype "bidirectional"))
    )
    (net (code "118") (name "unconnected-(U$3-PadMIC_BIAS)") (class "Default")
      (node (ref "U$3") (pin "MIC_BIAS") (pinfunction "MIC_BIAS_MIC_BIAS") (pintype "bidirectional"))
    )
    (net (code "119") (name "unconnected-(U$3-PadPCM_CLK)") (class "Default")
      (node (ref "U$3") (pin "PCM_CLK") (pinfunction "PCM_CLK_PCM_CLK") (pintype "bidirectional"))
    )
    (net (code "120") (name "unconnected-(U$3-PadPCM_IN)") (class "Default")
      (node (ref "U$3") (pin "PCM_IN") (pinfunction "PCM_IN_PCM_IN") (pintype "bidirectional"))
    )
    (net (code "121") (name "unconnected-(U$3-PadPCM_OUT)") (class "Default")
      (node (ref "U$3") (pin "PCM_OUT") (pinfunction "PCM_OUT_PCM_OUT") (pintype "bidirectional"))
    )
    (net (code "122") (name "unconnected-(U$3-PadPCM_SYNC)") (class "Default")
      (node (ref "U$3") (pin "PCM_SYNC") (pinfunction "PCM_SYNC_PCM_SYNC") (pintype "bidirectional"))
    )
    (net (code "123") (name "unconnected-(U$3-PadSPI_MISO)") (class "Default")
      (node (ref "U$3") (pin "SPI_MISO") (pinfunction "SPI_MISO_SPI_MISO") (pintype "bidirectional"))
    )
    (net (code "124") (name "unconnected-(U$3-PadSPI_MOSI)") (class "Default")
      (node (ref "U$3") (pin "SPI_MOSI") (pinfunction "SPI_MOSI_SPI_MOSI") (pintype "bidirectional"))
    )
    (net (code "125") (name "unconnected-(U$3-PadSPI_SCK)") (class "Default")
      (node (ref "U$3") (pin "SPI_SCK") (pinfunction "SPI_SCK_SPI_SCK") (pintype "bidirectional"))
    )
    (net (code "126") (name "unconnected-(U$3-PadSPI_SS)") (class "Default")
      (node (ref "U$3") (pin "SPI_SS") (pinfunction "SPI_SS_SPI_SS") (pintype "bidirectional"))
    )
    (net (code "127") (name "unconnected-(U$3-PadUART_CTS)") (class "Default")
      (node (ref "U$3") (pin "UART_CTS") (pinfunction "UART_CTS_UART_CTS") (pintype "bidirectional"))
    )
    (net (code "128") (name "unconnected-(U$3-PadUART_RTS)") (class "Default")
      (node (ref "U$3") (pin "UART_RTS") (pinfunction "UART_RTS_UART_RTS") (pintype "bidirectional"))
    )
  )
)
